# Porsche_Quad_Gauge.net
KiCad netlist of a schematic drawn in EAGLE
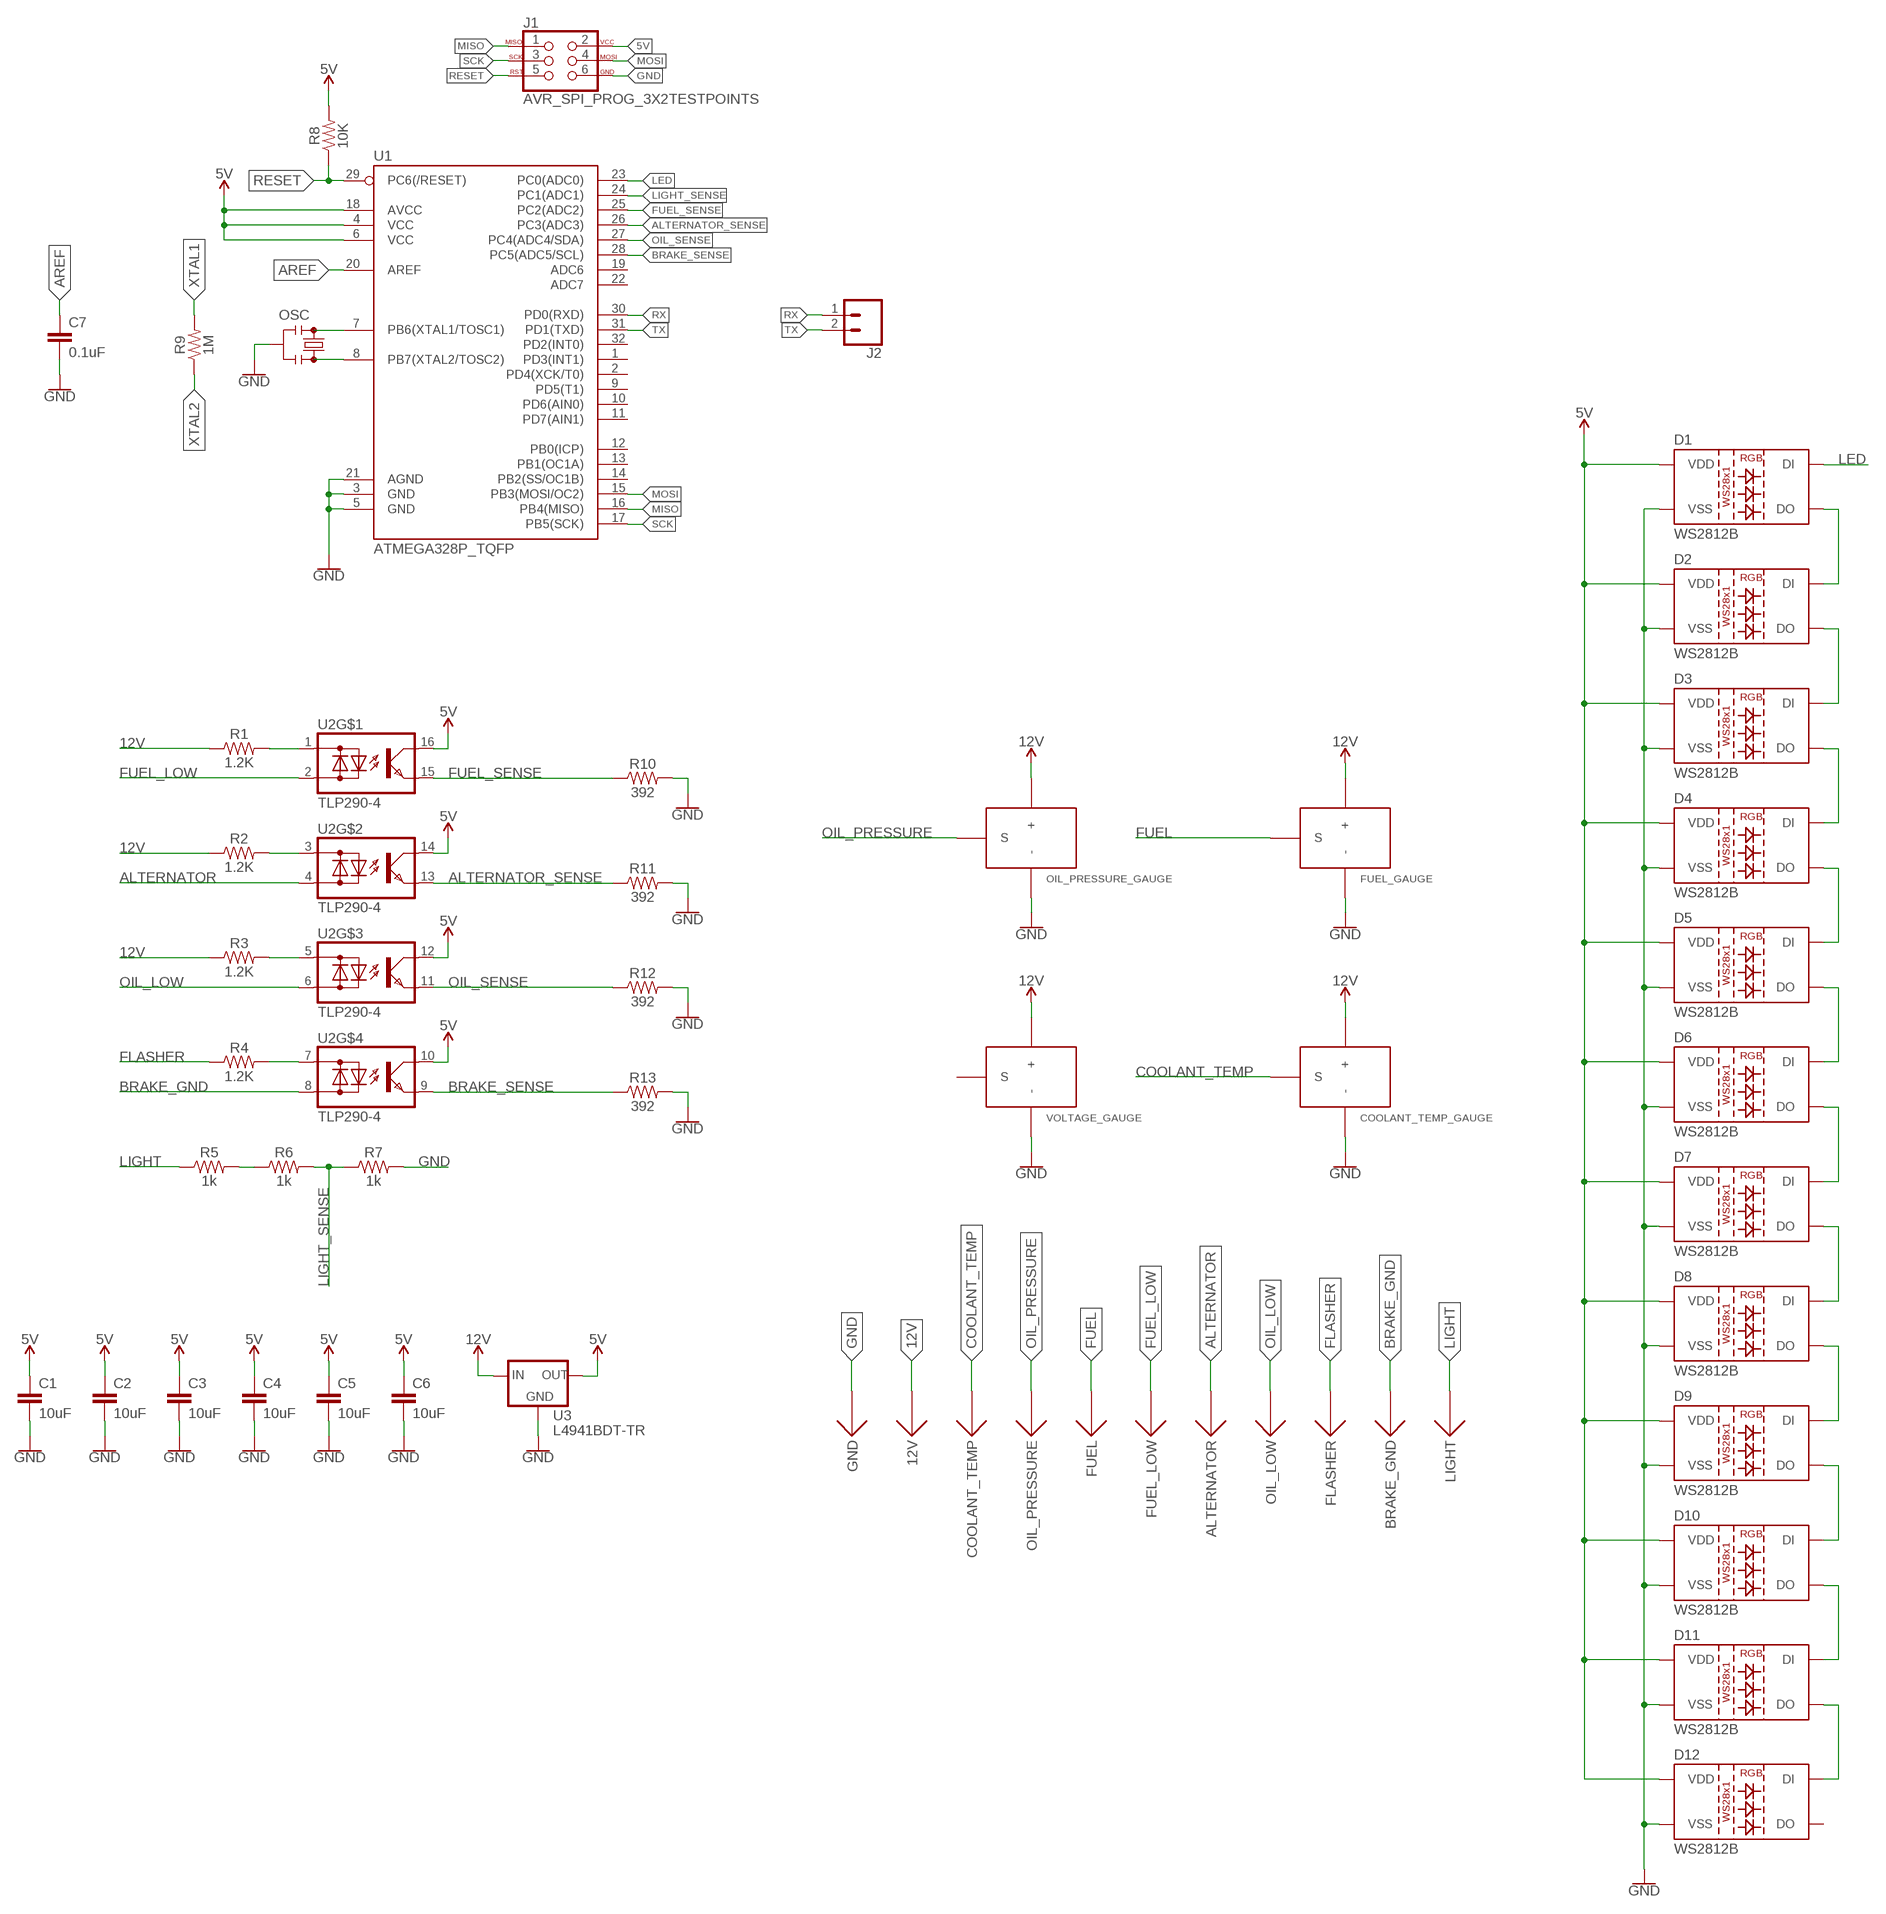
[diagram p0: schematic, sheet 1]

(export (version "E")
  (design (tool "Eeschema 10.0.6"))
  (components
    (comp (ref "12V")
      (value "CONNECTOR_QC_TAB_0.25")
      (footprint "eagle-import:CONNECTOR_QC_TAB-0.25")
      (libsource (lib "eagle-import") (part "CONNECTOR_QC_TAB_0.25"))
    )
    (comp (ref "ALTERNATOR")
      (value "CONNECTOR_QC_TAB_0.25")
      (footprint "eagle-import:CONNECTOR_QC_TAB-0.25")
      (libsource (lib "eagle-import") (part "CONNECTOR_QC_TAB_0.25"))
    )
    (comp (ref "BRAKE_GND")
      (value "CONNECTOR_QC_TAB_0.25")
      (footprint "eagle-import:CONNECTOR_QC_TAB-0.25")
      (libsource (lib "eagle-import") (part "CONNECTOR_QC_TAB_0.25"))
    )
    (comp (ref "C1")
      (value "10uF")
      (footprint "eagle-import:0805")
      (libsource (lib "eagle-import") (part "10UF-0805-10V-10%"))
    )
    (comp (ref "C2")
      (value "10uF")
      (footprint "eagle-import:0805")
      (libsource (lib "eagle-import") (part "10UF-0805-10V-10%"))
    )
    (comp (ref "C3")
      (value "10uF")
      (footprint "eagle-import:0805")
      (libsource (lib "eagle-import") (part "10UF-0805-10V-10%"))
    )
    (comp (ref "C4")
      (value "10uF")
      (footprint "eagle-import:0805")
      (libsource (lib "eagle-import") (part "10UF-0805-10V-10%"))
    )
    (comp (ref "C5")
      (value "10uF")
      (footprint "eagle-import:0805")
      (libsource (lib "eagle-import") (part "10UF-0805-10V-10%"))
    )
    (comp (ref "C6")
      (value "10uF")
      (footprint "eagle-import:0805")
      (libsource (lib "eagle-import") (part "10UF-0805-10V-10%"))
    )
    (comp (ref "C7")
      (value "0.1uF")
      (footprint "eagle-import:0805")
      (libsource (lib "eagle-import") (part "10UF-0805-10V-10%"))
    )
    (comp (ref "COOLANT_TEMP")
      (value "CONNECTOR_QC_TAB_0.25")
      (footprint "eagle-import:CONNECTOR_QC_TAB-0.25")
      (libsource (lib "eagle-import") (part "CONNECTOR_QC_TAB_0.25"))
    )
    (comp (ref "COOLANT_TEMP_GAUGE")
      (value "VDO_OLD")
      (footprint "eagle-import:VDO_GAUGE_SOCKET")
      (libsource (lib "eagle-import") (part "VDO_OLD"))
    )
    (comp (ref "D1")
      (value "WS2812B")
      (footprint "eagle-import:WS2812B")
      (libsource (lib "eagle-import") (part "WS2812B"))
    )
    (comp (ref "D2")
      (value "WS2812B")
      (footprint "eagle-import:WS2812B")
      (libsource (lib "eagle-import") (part "WS2812B"))
    )
    (comp (ref "D3")
      (value "WS2812B")
      (footprint "eagle-import:WS2812B")
      (libsource (lib "eagle-import") (part "WS2812B"))
    )
    (comp (ref "D4")
      (value "WS2812B")
      (footprint "eagle-import:WS2812B")
      (libsource (lib "eagle-import") (part "WS2812B"))
    )
    (comp (ref "D5")
      (value "WS2812B")
      (footprint "eagle-import:WS2812B")
      (libsource (lib "eagle-import") (part "WS2812B"))
    )
    (comp (ref "D6")
      (value "WS2812B")
      (footprint "eagle-import:WS2812B")
      (libsource (lib "eagle-import") (part "WS2812B"))
    )
    (comp (ref "D7")
      (value "WS2812B")
      (footprint "eagle-import:WS2812B")
      (libsource (lib "eagle-import") (part "WS2812B"))
    )
    (comp (ref "D8")
      (value "WS2812B")
      (footprint "eagle-import:WS2812B")
      (libsource (lib "eagle-import") (part "WS2812B"))
    )
    (comp (ref "D9")
      (value "WS2812B")
      (footprint "eagle-import:WS2812B")
      (libsource (lib "eagle-import") (part "WS2812B"))
    )
    (comp (ref "D10")
      (value "WS2812B")
      (footprint "eagle-import:WS2812B")
      (libsource (lib "eagle-import") (part "WS2812B"))
    )
    (comp (ref "D11")
      (value "WS2812B")
      (footprint "eagle-import:WS2812B")
      (libsource (lib "eagle-import") (part "WS2812B"))
    )
    (comp (ref "D12")
      (value "WS2812B")
      (footprint "eagle-import:WS2812B")
      (libsource (lib "eagle-import") (part "WS2812B"))
    )
    (comp (ref "FLASHER")
      (value "CONNECTOR_QC_TAB_0.25")
      (footprint "eagle-import:CONNECTOR_QC_TAB-0.25")
      (libsource (lib "eagle-import") (part "CONNECTOR_QC_TAB_0.25"))
    )
    (comp (ref "FUEL")
      (value "CONNECTOR_QC_TAB_0.25")
      (footprint "eagle-import:CONNECTOR_QC_TAB-0.25")
      (libsource (lib "eagle-import") (part "CONNECTOR_QC_TAB_0.25"))
    )
    (comp (ref "FUEL_GAUGE")
      (value "VDO_OLD")
      (footprint "eagle-import:VDO_GAUGE_SOCKET")
      (libsource (lib "eagle-import") (part "VDO_OLD"))
    )
    (comp (ref "FUEL_LOW")
      (value "CONNECTOR_QC_TAB_0.25")
      (footprint "eagle-import:CONNECTOR_QC_TAB-0.25")
      (libsource (lib "eagle-import") (part "CONNECTOR_QC_TAB_0.25"))
    )
    (comp (ref "GND")
      (value "CONNECTOR_QC_TAB_0.25")
      (footprint "eagle-import:CONNECTOR_QC_TAB-0.25")
      (libsource (lib "eagle-import") (part "CONNECTOR_QC_TAB_0.25"))
    )
    (comp (ref "J1")
      (value "AVR_SPI_PROG_3X2TESTPOINTS")
      (footprint "eagle-import:2X3_TEST_POINTS")
      (libsource (lib "eagle-import") (part "AVR_SPI_PROG_3X2TESTPOINTS"))
    )
    (comp (ref "J2")
      (value "CONN_02")
      (footprint "eagle-import:1X02")
      (libsource (lib "eagle-import") (part "CONN_02"))
    )
    (comp (ref "LIGHT")
      (value "CONNECTOR_QC_TAB_0.25")
      (footprint "eagle-import:CONNECTOR_QC_TAB-0.25")
      (libsource (lib "eagle-import") (part "CONNECTOR_QC_TAB_0.25"))
    )
    (comp (ref "OIL_LOW")
      (value "CONNECTOR_QC_TAB_0.25")
      (footprint "eagle-import:CONNECTOR_QC_TAB-0.25")
      (libsource (lib "eagle-import") (part "CONNECTOR_QC_TAB_0.25"))
    )
    (comp (ref "OIL_PRESSURE")
      (value "CONNECTOR_QC_TAB_0.25")
      (footprint "eagle-import:CONNECTOR_QC_TAB-0.25")
      (libsource (lib "eagle-import") (part "CONNECTOR_QC_TAB_0.25"))
    )
    (comp (ref "OIL_PRESSURE_GAUGE")
      (value "VDO_NEW")
      (footprint "eagle-import:VDO_NEW_GAUGE_SOCKET")
      (libsource (lib "eagle-import") (part "VDO_NEW"))
    )
    (comp (ref "OSC")
      (value "PRQC16.00SR1010V00L")
      (footprint "eagle-import:3-SMD")
      (libsource (lib "eagle-import") (part "PRQC16.00SR1010V00L"))
    )
    (comp (ref "R1")
      (value "1.2K")
      (footprint "eagle-import:0805")
      (libsource (lib "eagle-import") (part "RESISTOR0805"))
    )
    (comp (ref "R2")
      (value "1.2K")
      (footprint "eagle-import:0805")
      (libsource (lib "eagle-import") (part "RESISTOR0805"))
    )
    (comp (ref "R3")
      (value "1.2K")
      (footprint "eagle-import:0805")
      (libsource (lib "eagle-import") (part "RESISTOR0805"))
    )
    (comp (ref "R4")
      (value "1.2K")
      (footprint "eagle-import:0805")
      (libsource (lib "eagle-import") (part "RESISTOR0805"))
    )
    (comp (ref "R5")
      (value "1k")
      (footprint "eagle-import:0805")
      (libsource (lib "eagle-import") (part "RESISTOR0805"))
    )
    (comp (ref "R6")
      (value "1k")
      (footprint "eagle-import:0805")
      (libsource (lib "eagle-import") (part "RESISTOR0805"))
    )
    (comp (ref "R7")
      (value "1k")
      (footprint "eagle-import:0805")
      (libsource (lib "eagle-import") (part "RESISTOR0805"))
    )
    (comp (ref "R8")
      (value "10K")
      (footprint "eagle-import:0805")
      (libsource (lib "eagle-import") (part "RESISTOR0805"))
    )
    (comp (ref "R9")
      (value "1M")
      (footprint "eagle-import:0805")
      (libsource (lib "eagle-import") (part "RESISTOR0805"))
    )
    (comp (ref "R10")
      (value "392")
      (footprint "eagle-import:0805")
      (libsource (lib "eagle-import") (part "RESISTOR0805"))
    )
    (comp (ref "R11")
      (value "392")
      (footprint "eagle-import:0805")
      (libsource (lib "eagle-import") (part "RESISTOR0805"))
    )
    (comp (ref "R12")
      (value "392")
      (footprint "eagle-import:0805")
      (libsource (lib "eagle-import") (part "RESISTOR0805"))
    )
    (comp (ref "R13")
      (value "392")
      (footprint "eagle-import:0805")
      (libsource (lib "eagle-import") (part "RESISTOR0805"))
    )
    (comp (ref "U1")
      (value "ATMEGA328P_TQFP")
      (footprint "eagle-import:TQFP32-08")
      (libsource (lib "eagle-import") (part "ATMEGA328P_TQFP"))
    )
    (comp (ref "U2")
      (value "TLP290-4")
      (footprint "eagle-import:SO16")
      (libsource (lib "eagle-import") (part "TLP290-4"))
    )
    (comp (ref "U3")
      (value "L4941BDT-TR")
      (footprint "eagle-import:D-PAK_TO252AA")
      (libsource (lib "eagle-import") (part "L4941BDT-TR"))
    )
    (comp (ref "VOLTAGE_GAUGE")
      (value "VDO_NEW")
      (footprint "eagle-import:VDO_NEW_GAUGE_SOCKET")
      (libsource (lib "eagle-import") (part "VDO_NEW"))
    )
  )
  (nets
    (net (code "1") (name "5V") (class "Default")
      (node (ref "C1") (pin "1") (pinfunction "1_1") (pintype "passive"))
      (node (ref "C2") (pin "1") (pinfunction "1_1") (pintype "passive"))
      (node (ref "C3") (pin "1") (pinfunction "1_1") (pintype "passive"))
      (node (ref "C4") (pin "1") (pinfunction "1_1") (pintype "passive"))
      (node (ref "C5") (pin "1") (pinfunction "1_1") (pintype "passive"))
      (node (ref "C6") (pin "1") (pinfunction "1_1") (pintype "passive"))
      (node (ref "D1") (pin "1") (pinfunction "VDD_1") (pintype "bidirectional"))
      (node (ref "D10") (pin "1") (pinfunction "VDD_1") (pintype "bidirectional"))
      (node (ref "D11") (pin "1") (pinfunction "VDD_1") (pintype "bidirectional"))
      (node (ref "D12") (pin "1") (pinfunction "VDD_1") (pintype "bidirectional"))
      (node (ref "D2") (pin "1") (pinfunction "VDD_1") (pintype "bidirectional"))
      (node (ref "D3") (pin "1") (pinfunction "VDD_1") (pintype "bidirectional"))
      (node (ref "D4") (pin "1") (pinfunction "VDD_1") (pintype "bidirectional"))
      (node (ref "D5") (pin "1") (pinfunction "VDD_1") (pintype "bidirectional"))
      (node (ref "D6") (pin "1") (pinfunction "VDD_1") (pintype "bidirectional"))
      (node (ref "D7") (pin "1") (pinfunction "VDD_1") (pintype "bidirectional"))
      (node (ref "D8") (pin "1") (pinfunction "VDD_1") (pintype "bidirectional"))
      (node (ref "D9") (pin "1") (pinfunction "VDD_1") (pintype "bidirectional"))
      (node (ref "J1") (pin "2") (pinfunction "2_2") (pintype "passive"))
      (node (ref "R8") (pin "2") (pinfunction "2_2") (pintype "passive"))
      (node (ref "U1") (pin "18") (pinfunction "AVCC_18") (pintype "bidirectional"))
      (node (ref "U1") (pin "4") (pinfunction "VCC_4") (pintype "bidirectional"))
      (node (ref "U1") (pin "6") (pinfunction "VCC_6") (pintype "bidirectional"))
      (node (ref "U2") (pin "10") (pinfunction "C_10") (pintype "passive"))
      (node (ref "U2") (pin "12") (pinfunction "C_12") (pintype "passive"))
      (node (ref "U2") (pin "14") (pinfunction "C_14") (pintype "passive"))
      (node (ref "U2") (pin "16") (pinfunction "C_16") (pintype "passive"))
      (node (ref "U3") (pin "3") (pinfunction "OUT_3") (pintype "passive"))
    )
    (net (code "2") (name "12V") (class "Default")
      (node (ref "12V") (pin "S1") (pinfunction "SIGNAL_S1") (pintype "bidirectional"))
      (node (ref "12V") (pin "S2") (pinfunction "SIGNAL_S2") (pintype "bidirectional"))
      (node (ref "COOLANT_TEMP_GAUGE") (pin "12V") (pinfunction "+_12V") (pintype "bidirectional"))
      (node (ref "FUEL_GAUGE") (pin "12V") (pinfunction "+_12V") (pintype "bidirectional"))
      (node (ref "OIL_PRESSURE_GAUGE") (pin "12V") (pinfunction "+_12V") (pintype "bidirectional"))
      (node (ref "R1") (pin "1") (pinfunction "1_1") (pintype "passive"))
      (node (ref "R2") (pin "1") (pinfunction "1_1") (pintype "passive"))
      (node (ref "R3") (pin "1") (pinfunction "1_1") (pintype "passive"))
      (node (ref "U3") (pin "1") (pinfunction "IN_1") (pintype "input"))
      (node (ref "VOLTAGE_GAUGE") (pin "12V") (pinfunction "+_12V") (pintype "bidirectional"))
    )
    (net (code "3") (name "ALTERNATOR") (class "Default")
      (node (ref "ALTERNATOR") (pin "S1") (pinfunction "SIGNAL_S1") (pintype "bidirectional"))
      (node (ref "ALTERNATOR") (pin "S2") (pinfunction "SIGNAL_S2") (pintype "bidirectional"))
      (node (ref "U2") (pin "4") (pinfunction "AC2_4") (pintype "passive"))
    )
    (net (code "4") (name "ALTERNATOR_SENSE") (class "Default")
      (node (ref "R11") (pin "1") (pinfunction "1_1") (pintype "passive"))
      (node (ref "U1") (pin "26") (pinfunction "PC3(ADC3)_26") (pintype "bidirectional"))
      (node (ref "U2") (pin "13") (pinfunction "E_13") (pintype "passive"))
    )
    (net (code "5") (name "AREF") (class "Default")
      (node (ref "C7") (pin "1") (pinfunction "1_1") (pintype "passive"))
      (node (ref "U1") (pin "20") (pinfunction "AREF_20") (pintype "bidirectional"))
    )
    (net (code "6") (name "BRAKE_GND") (class "Default")
      (node (ref "BRAKE_GND") (pin "S1") (pinfunction "SIGNAL_S1") (pintype "bidirectional"))
      (node (ref "BRAKE_GND") (pin "S2") (pinfunction "SIGNAL_S2") (pintype "bidirectional"))
      (node (ref "U2") (pin "8") (pinfunction "AC2_8") (pintype "passive"))
    )
    (net (code "7") (name "BRAKE_SENSE") (class "Default")
      (node (ref "R13") (pin "1") (pinfunction "1_1") (pintype "passive"))
      (node (ref "U1") (pin "28") (pinfunction "PC5(ADC5/SCL)_28") (pintype "bidirectional"))
      (node (ref "U2") (pin "9") (pinfunction "E_9") (pintype "passive"))
    )
    (net (code "8") (name "COOLANT_TEMP") (class "Default")
      (node (ref "COOLANT_TEMP") (pin "S1") (pinfunction "SIGNAL_S1") (pintype "bidirectional"))
      (node (ref "COOLANT_TEMP") (pin "S2") (pinfunction "SIGNAL_S2") (pintype "bidirectional"))
      (node (ref "COOLANT_TEMP_GAUGE") (pin "SIGNAL") (pinfunction "S_SIGNAL") (pintype "bidirectional"))
    )
    (net (code "9") (name "FLASHER") (class "Default")
      (node (ref "FLASHER") (pin "S1") (pinfunction "SIGNAL_S1") (pintype "bidirectional"))
      (node (ref "FLASHER") (pin "S2") (pinfunction "SIGNAL_S2") (pintype "bidirectional"))
      (node (ref "R4") (pin "1") (pinfunction "1_1") (pintype "passive"))
    )
    (net (code "10") (name "FUEL") (class "Default")
      (node (ref "FUEL") (pin "S1") (pinfunction "SIGNAL_S1") (pintype "bidirectional"))
      (node (ref "FUEL") (pin "S2") (pinfunction "SIGNAL_S2") (pintype "bidirectional"))
      (node (ref "FUEL_GAUGE") (pin "SIGNAL") (pinfunction "S_SIGNAL") (pintype "bidirectional"))
    )
    (net (code "11") (name "FUEL_LOW") (class "Default")
      (node (ref "FUEL_LOW") (pin "S1") (pinfunction "SIGNAL_S1") (pintype "bidirectional"))
      (node (ref "FUEL_LOW") (pin "S2") (pinfunction "SIGNAL_S2") (pintype "bidirectional"))
      (node (ref "U2") (pin "2") (pinfunction "AC2_2") (pintype "passive"))
    )
    (net (code "12") (name "FUEL_SENSE") (class "Default")
      (node (ref "R10") (pin "1") (pinfunction "1_1") (pintype "passive"))
      (node (ref "U1") (pin "25") (pinfunction "PC2(ADC2)_25") (pintype "bidirectional"))
      (node (ref "U2") (pin "15") (pinfunction "E_15") (pintype "passive"))
    )
    (net (code "13") (name "GND") (class "Default")
      (node (ref "C1") (pin "2") (pinfunction "2_2") (pintype "passive"))
      (node (ref "C2") (pin "2") (pinfunction "2_2") (pintype "passive"))
      (node (ref "C3") (pin "2") (pinfunction "2_2") (pintype "passive"))
      (node (ref "C4") (pin "2") (pinfunction "2_2") (pintype "passive"))
      (node (ref "C5") (pin "2") (pinfunction "2_2") (pintype "passive"))
      (node (ref "C6") (pin "2") (pinfunction "2_2") (pintype "passive"))
      (node (ref "C7") (pin "2") (pinfunction "2_2") (pintype "passive"))
      (node (ref "COOLANT_TEMP_GAUGE") (pin "GND") (pinfunction "-_GND") (pintype "bidirectional"))
      (node (ref "D1") (pin "3") (pinfunction "VSS_3") (pintype "bidirectional"))
      (node (ref "D10") (pin "3") (pinfunction "VSS_3") (pintype "bidirectional"))
      (node (ref "D11") (pin "3") (pinfunction "VSS_3") (pintype "bidirectional"))
      (node (ref "D12") (pin "3") (pinfunction "VSS_3") (pintype "bidirectional"))
      (node (ref "D2") (pin "3") (pinfunction "VSS_3") (pintype "bidirectional"))
      (node (ref "D3") (pin "3") (pinfunction "VSS_3") (pintype "bidirectional"))
      (node (ref "D4") (pin "3") (pinfunction "VSS_3") (pintype "bidirectional"))
      (node (ref "D5") (pin "3") (pinfunction "VSS_3") (pintype "bidirectional"))
      (node (ref "D6") (pin "3") (pinfunction "VSS_3") (pintype "bidirectional"))
      (node (ref "D7") (pin "3") (pinfunction "VSS_3") (pintype "bidirectional"))
      (node (ref "D8") (pin "3") (pinfunction "VSS_3") (pintype "bidirectional"))
      (node (ref "D9") (pin "3") (pinfunction "VSS_3") (pintype "bidirectional"))
      (node (ref "FUEL_GAUGE") (pin "GND") (pinfunction "-_GND") (pintype "bidirectional"))
      (node (ref "GND") (pin "S1") (pinfunction "SIGNAL_S1") (pintype "bidirectional"))
      (node (ref "GND") (pin "S2") (pinfunction "SIGNAL_S2") (pintype "bidirectional"))
      (node (ref "J1") (pin "6") (pinfunction "6_6") (pintype "passive"))
      (node (ref "OIL_PRESSURE_GAUGE") (pin "GND") (pinfunction "-_GND") (pintype "bidirectional"))
      (node (ref "OSC") (pin "GND") (pinfunction "2_GND") (pintype "passive"))
      (node (ref "R10") (pin "2") (pinfunction "2_2") (pintype "passive"))
      (node (ref "R11") (pin "2") (pinfunction "2_2") (pintype "passive"))
      (node (ref "R12") (pin "2") (pinfunction "2_2") (pintype "passive"))
      (node (ref "R13") (pin "2") (pinfunction "2_2") (pintype "passive"))
      (node (ref "R7") (pin "2") (pinfunction "2_2") (pintype "passive"))
      (node (ref "U1") (pin "21") (pinfunction "AGND_21") (pintype "bidirectional"))
      (node (ref "U1") (pin "3") (pinfunction "GND_3") (pintype "bidirectional"))
      (node (ref "U1") (pin "5") (pinfunction "GND_5") (pintype "bidirectional"))
      (node (ref "U3") (pin "2") (pinfunction "GND_2") (pintype "input"))
      (node (ref "VOLTAGE_GAUGE") (pin "GND") (pinfunction "-_GND") (pintype "bidirectional"))
    )
    (net (code "14") (name "LED") (class "Default")
      (node (ref "D1") (pin "4") (pinfunction "DI_4") (pintype "bidirectional"))
      (node (ref "U1") (pin "23") (pinfunction "PC0(ADC0)_23") (pintype "bidirectional"))
    )
    (net (code "15") (name "LIGHT") (class "Default")
      (node (ref "LIGHT") (pin "S1") (pinfunction "SIGNAL_S1") (pintype "bidirectional"))
      (node (ref "LIGHT") (pin "S2") (pinfunction "SIGNAL_S2") (pintype "bidirectional"))
      (node (ref "R5") (pin "1") (pinfunction "1_1") (pintype "passive"))
    )
    (net (code "16") (name "LIGHT_SENSE") (class "Default")
      (node (ref "R6") (pin "2") (pinfunction "2_2") (pintype "passive"))
      (node (ref "R7") (pin "1") (pinfunction "1_1") (pintype "passive"))
      (node (ref "U1") (pin "24") (pinfunction "PC1(ADC1)_24") (pintype "bidirectional"))
    )
    (net (code "17") (name "MISO") (class "Default")
      (node (ref "J1") (pin "1") (pinfunction "1_1") (pintype "passive"))
      (node (ref "U1") (pin "16") (pinfunction "PB4(MISO)_16") (pintype "bidirectional"))
    )
    (net (code "18") (name "MOSI") (class "Default")
      (node (ref "J1") (pin "4") (pinfunction "4_4") (pintype "passive"))
      (node (ref "U1") (pin "15") (pinfunction "PB3(MOSI/OC2)_15") (pintype "bidirectional"))
    )
    (net (code "19") (name "Net-(D1-DO)") (class "Default")
      (node (ref "D1") (pin "2") (pinfunction "DO_2") (pintype "bidirectional"))
      (node (ref "D2") (pin "4") (pinfunction "DI_4") (pintype "bidirectional"))
    )
    (net (code "20") (name "Net-(D2-DO)") (class "Default")
      (node (ref "D2") (pin "2") (pinfunction "DO_2") (pintype "bidirectional"))
      (node (ref "D3") (pin "4") (pinfunction "DI_4") (pintype "bidirectional"))
    )
    (net (code "21") (name "Net-(D3-DO)") (class "Default")
      (node (ref "D3") (pin "2") (pinfunction "DO_2") (pintype "bidirectional"))
      (node (ref "D4") (pin "4") (pinfunction "DI_4") (pintype "bidirectional"))
    )
    (net (code "22") (name "Net-(D4-DO)") (class "Default")
      (node (ref "D4") (pin "2") (pinfunction "DO_2") (pintype "bidirectional"))
      (node (ref "D5") (pin "4") (pinfunction "DI_4") (pintype "bidirectional"))
    )
    (net (code "23") (name "Net-(D5-DO)") (class "Default")
      (node (ref "D5") (pin "2") (pinfunction "DO_2") (pintype "bidirectional"))
      (node (ref "D6") (pin "4") (pinfunction "DI_4") (pintype "bidirectional"))
    )
    (net (code "24") (name "Net-(D6-DO)") (class "Default")
      (node (ref "D6") (pin "2") (pinfunction "DO_2") (pintype "bidirectional"))
      (node (ref "D7") (pin "4") (pinfunction "DI_4") (pintype "bidirectional"))
    )
    (net (code "25") (name "Net-(D7-DO)") (class "Default")
      (node (ref "D7") (pin "2") (pinfunction "DO_2") (pintype "bidirectional"))
      (node (ref "D8") (pin "4") (pinfunction "DI_4") (pintype "bidirectional"))
    )
    (net (code "26") (name "Net-(D8-DO)") (class "Default")
      (node (ref "D8") (pin "2") (pinfunction "DO_2") (pintype "bidirectional"))
      (node (ref "D9") (pin "4") (pinfunction "DI_4") (pintype "bidirectional"))
    )
    (net (code "27") (name "Net-(D10-DI)") (class "Default")
      (node (ref "D10") (pin "4") (pinfunction "DI_4") (pintype "bidirectional"))
      (node (ref "D9") (pin "2") (pinfunction "DO_2") (pintype "bidirectional"))
    )
    (net (code "28") (name "Net-(D10-DO)") (class "Default")
      (node (ref "D10") (pin "2") (pinfunction "DO_2") (pintype "bidirectional"))
      (node (ref "D11") (pin "4") (pinfunction "DI_4") (pintype "bidirectional"))
    )
    (net (code "29") (name "Net-(D11-DO)") (class "Default")
      (node (ref "D11") (pin "2") (pinfunction "DO_2") (pintype "bidirectional"))
      (node (ref "D12") (pin "4") (pinfunction "DI_4") (pintype "bidirectional"))
    )
    (net (code "30") (name "Net-(R5-Pad2)") (class "Default")
      (node (ref "R5") (pin "2") (pinfunction "2_2") (pintype "passive"))
      (node (ref "R6") (pin "1") (pinfunction "1_1") (pintype "passive"))
    )
    (net (code "31") (name "Net-(U2A-AC1)") (class "Default")
      (node (ref "R1") (pin "2") (pinfunction "2_2") (pintype "passive"))
      (node (ref "U2") (pin "1") (pinfunction "AC1_1") (pintype "passive"))
    )
    (net (code "32") (name "Net-(U2B-AC1)") (class "Default")
      (node (ref "R2") (pin "2") (pinfunction "2_2") (pintype "passive"))
      (node (ref "U2") (pin "3") (pinfunction "AC1_3") (pintype "passive"))
    )
    (net (code "33") (name "Net-(U2C-AC1)") (class "Default")
      (node (ref "R3") (pin "2") (pinfunction "2_2") (pintype "passive"))
      (node (ref "U2") (pin "5") (pinfunction "AC1_5") (pintype "passive"))
    )
    (net (code "34") (name "Net-(U2D-AC1)") (class "Default")
      (node (ref "R4") (pin "2") (pinfunction "2_2") (pintype "passive"))
      (node (ref "U2") (pin "7") (pinfunction "AC1_7") (pintype "passive"))
    )
    (net (code "35") (name "OIL_LOW") (class "Default")
      (node (ref "OIL_LOW") (pin "S1") (pinfunction "SIGNAL_S1") (pintype "bidirectional"))
      (node (ref "OIL_LOW") (pin "S2") (pinfunction "SIGNAL_S2") (pintype "bidirectional"))
      (node (ref "U2") (pin "6") (pinfunction "AC2_6") (pintype "passive"))
    )
    (net (code "36") (name "OIL_PRESSURE") (class "Default")
      (node (ref "OIL_PRESSURE") (pin "S1") (pinfunction "SIGNAL_S1") (pintype "bidirectional"))
      (node (ref "OIL_PRESSURE") (pin "S2") (pinfunction "SIGNAL_S2") (pintype "bidirectional"))
      (node (ref "OIL_PRESSURE_GAUGE") (pin "SIGNAL") (pinfunction "S_SIGNAL") (pintype "bidirectional"))
    )
    (net (code "37") (name "OIL_SENSE") (class "Default")
      (node (ref "R12") (pin "1") (pinfunction "1_1") (pintype "passive"))
      (node (ref "U1") (pin "27") (pinfunction "PC4(ADC4/SDA)_27") (pintype "bidirectional"))
      (node (ref "U2") (pin "11") (pinfunction "E_11") (pintype "passive"))
    )
    (net (code "38") (name "RESET") (class "Default")
      (node (ref "J1") (pin "5") (pinfunction "5_5") (pintype "passive"))
      (node (ref "R8") (pin "1") (pinfunction "1_1") (pintype "passive"))
      (node (ref "U1") (pin "29") (pinfunction "PC6(/RESET)_29") (pintype "bidirectional"))
    )
    (net (code "39") (name "RX") (class "Default")
      (node (ref "J2") (pin "1") (pinfunction "1_1") (pintype "passive"))
      (node (ref "U1") (pin "30") (pinfunction "PD0(RXD)_30") (pintype "bidirectional"))
    )
    (net (code "40") (name "SCK") (class "Default")
      (node (ref "J1") (pin "3") (pinfunction "3_3") (pintype "passive"))
      (node (ref "U1") (pin "17") (pinfunction "PB5(SCK)_17") (pintype "bidirectional"))
    )
    (net (code "41") (name "TX") (class "Default")
      (node (ref "J2") (pin "2") (pinfunction "2_2") (pintype "passive"))
      (node (ref "U1") (pin "31") (pinfunction "PD1(TXD)_31") (pintype "bidirectional"))
    )
    (net (code "42") (name "XTAL1") (class "Default")
      (node (ref "OSC") (pin "XTAL1") (pinfunction "1_XTAL1") (pintype "passive"))
      (node (ref "R9") (pin "2") (pinfunction "2_2") (pintype "passive"))
      (node (ref "U1") (pin "7") (pinfunction "PB6(XTAL1/TOSC1)_7") (pintype "bidirectional"))
    )
    (net (code "43") (name "XTAL2") (class "Default")
      (node (ref "OSC") (pin "XTAL2") (pinfunction "3_XTAL2") (pintype "passive"))
      (node (ref "R9") (pin "1") (pinfunction "1_1") (pintype "passive"))
      (node (ref "U1") (pin "8") (pinfunction "PB7(XTAL2/TOSC2)_8") (pintype "bidirectional"))
    )
    (net (code "44") (name "unconnected-(D12-DO-Pad2)") (class "Default")
      (node (ref "D12") (pin "2") (pinfunction "DO_2") (pintype "bidirectional"))
    )
    (net (code "45") (name "unconnected-(U1-ADC6-Pad19)") (class "Default")
      (node (ref "U1") (pin "19") (pinfunction "ADC6_19") (pintype "bidirectional"))
    )
    (net (code "46") (name "unconnected-(U1-ADC7-Pad22)") (class "Default")
      (node (ref "U1") (pin "22") (pinfunction "ADC7_22") (pintype "bidirectional"))
    )
    (net (code "47") (name "unconnected-(U1-PB0(ICP)-Pad12)") (class "Default")
      (node (ref "U1") (pin "12") (pinfunction "PB0(ICP)_12") (pintype "bidirectional"))
    )
    (net (code "48") (name "unconnected-(U1-PB1(OC1A)-Pad13)") (class "Default")
      (node (ref "U1") (pin "13") (pinfunction "PB1(OC1A)_13") (pintype "bidirectional"))
    )
    (net (code "49") (name "unconnected-(U1-PB2(SS{slash}OC1B)-Pad14)") (class "Default")
      (node (ref "U1") (pin "14") (pinfunction "PB2(SS/OC1B)_14") (pintype "bidirectional"))
    )
    (net (code "50") (name "unconnected-(U1-PD2(INT0)-Pad32)") (class "Default")
      (node (ref "U1") (pin "32") (pinfunction "PD2(INT0)_32") (pintype "bidirectional"))
    )
    (net (code "51") (name "unconnected-(U1-PD3(INT1)-Pad1)") (class "Default")
      (node (ref "U1") (pin "1") (pinfunction "PD3(INT1)_1") (pintype "bidirectional"))
    )
    (net (code "52") (name "unconnected-(U1-PD4(XCK{slash}T0)-Pad2)") (class "Default")
      (node (ref "U1") (pin "2") (pinfunction "PD4(XCK/T0)_2") (pintype "bidirectional"))
    )
    (net (code "53") (name "unconnected-(U1-PD5(T1)-Pad9)") (class "Default")
      (node (ref "U1") (pin "9") (pinfunction "PD5(T1)_9") (pintype "bidirectional"))
    )
    (net (code "54") (name "unconnected-(U1-PD6(AIN0)-Pad10)") (class "Default")
      (node (ref "U1") (pin "10") (pinfunction "PD6(AIN0)_10") (pintype "bidirectional"))
    )
    (net (code "55") (name "unconnected-(U1-PD7(AIN1)-Pad11)") (class "Default")
      (node (ref "U1") (pin "11") (pinfunction "PD7(AIN1)_11") (pintype "bidirectional"))
    )
    (net (code "56") (name "unconnected-(VOLTAGE_GAUGE-S-PadSIGNAL)") (class "Default")
      (node (ref "VOLTAGE_GAUGE") (pin "SIGNAL") (pinfunction "S_SIGNAL") (pintype "bidirectional"))
    )
  )
)
